# ul-12.net
KiCad netlist of a schematic drawn in EAGLE
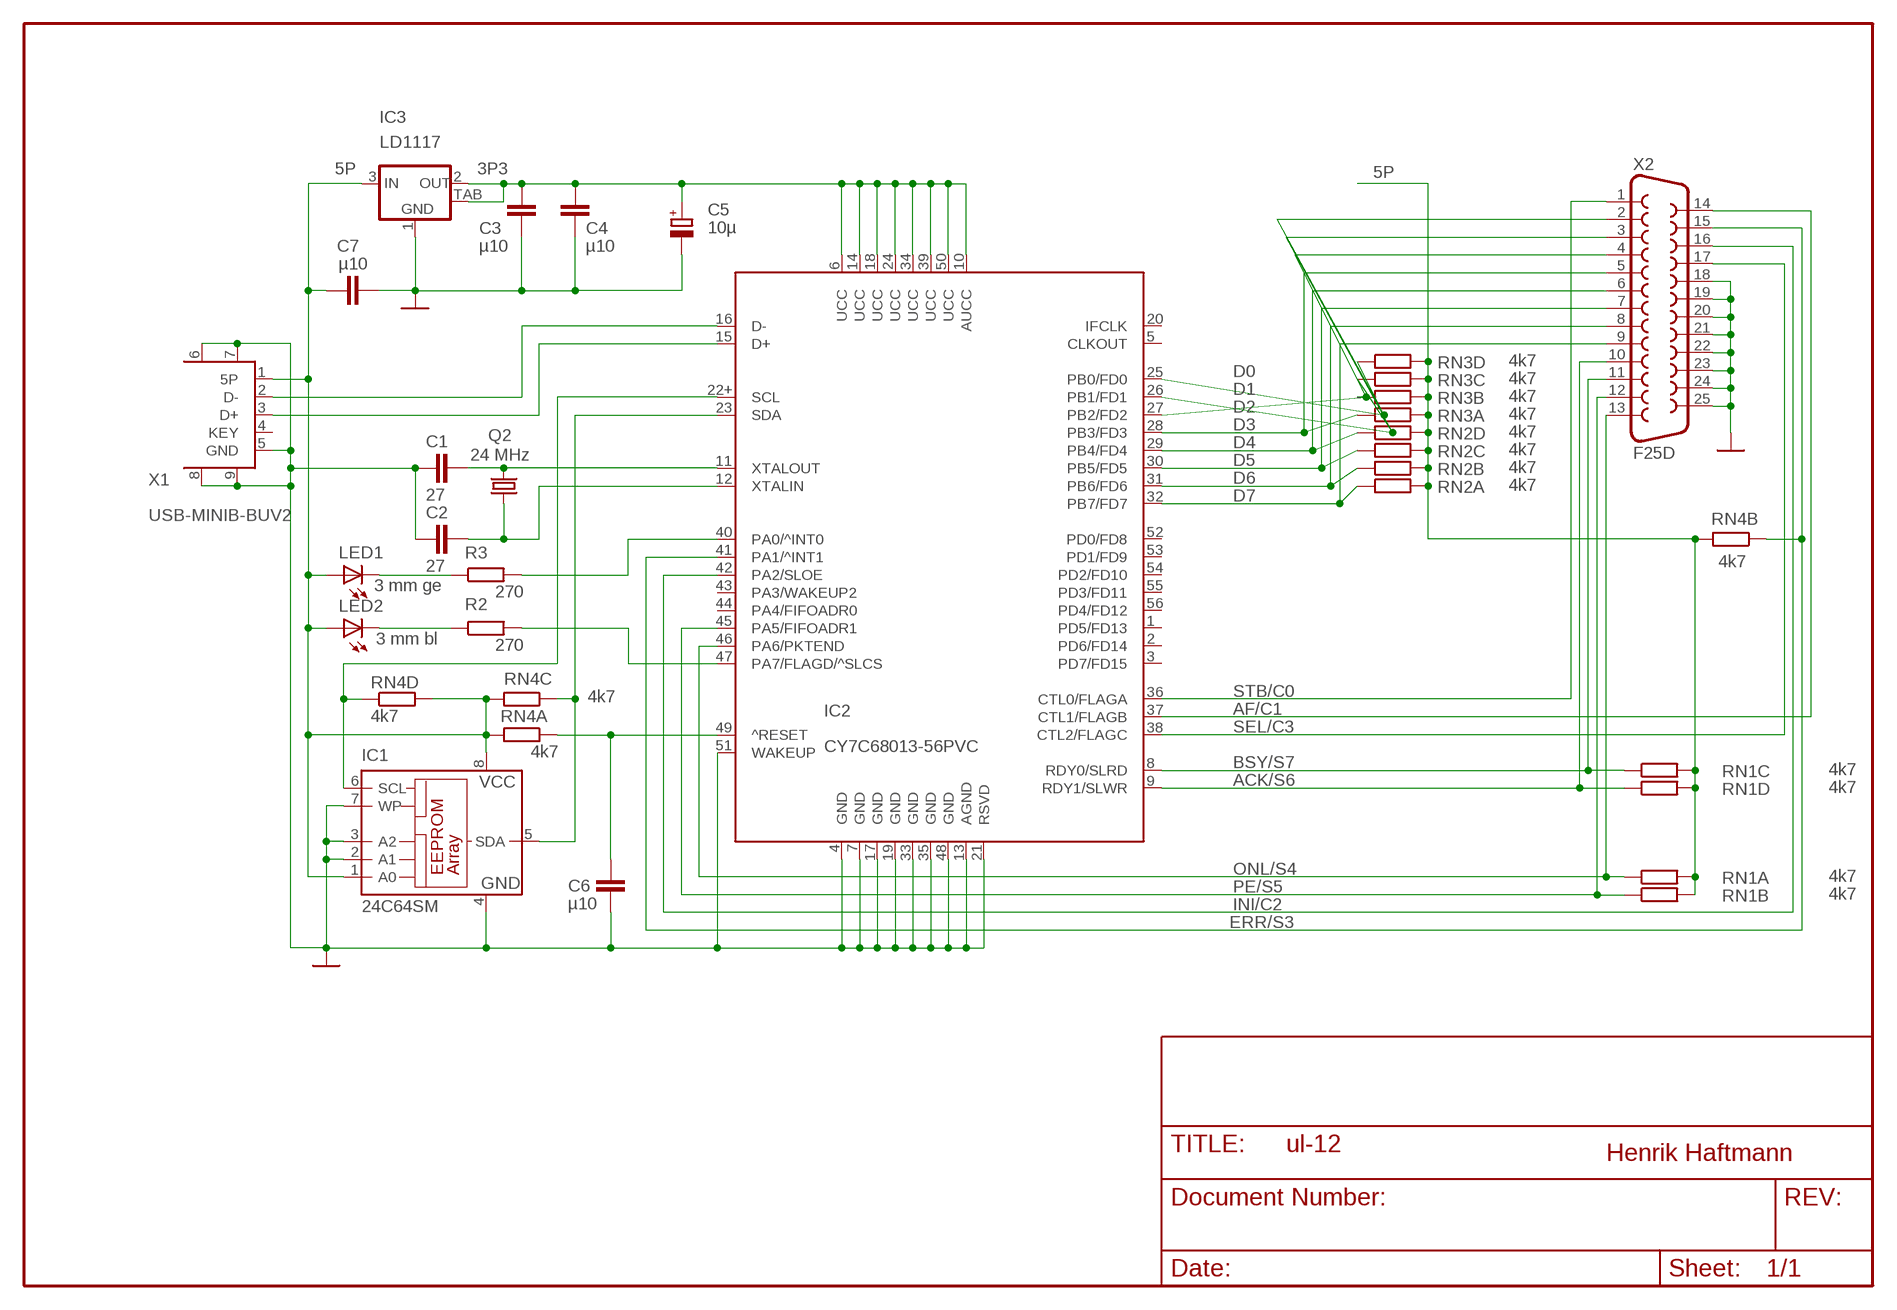
[diagram p0: schematic, sheet 1, part 1 of 2]
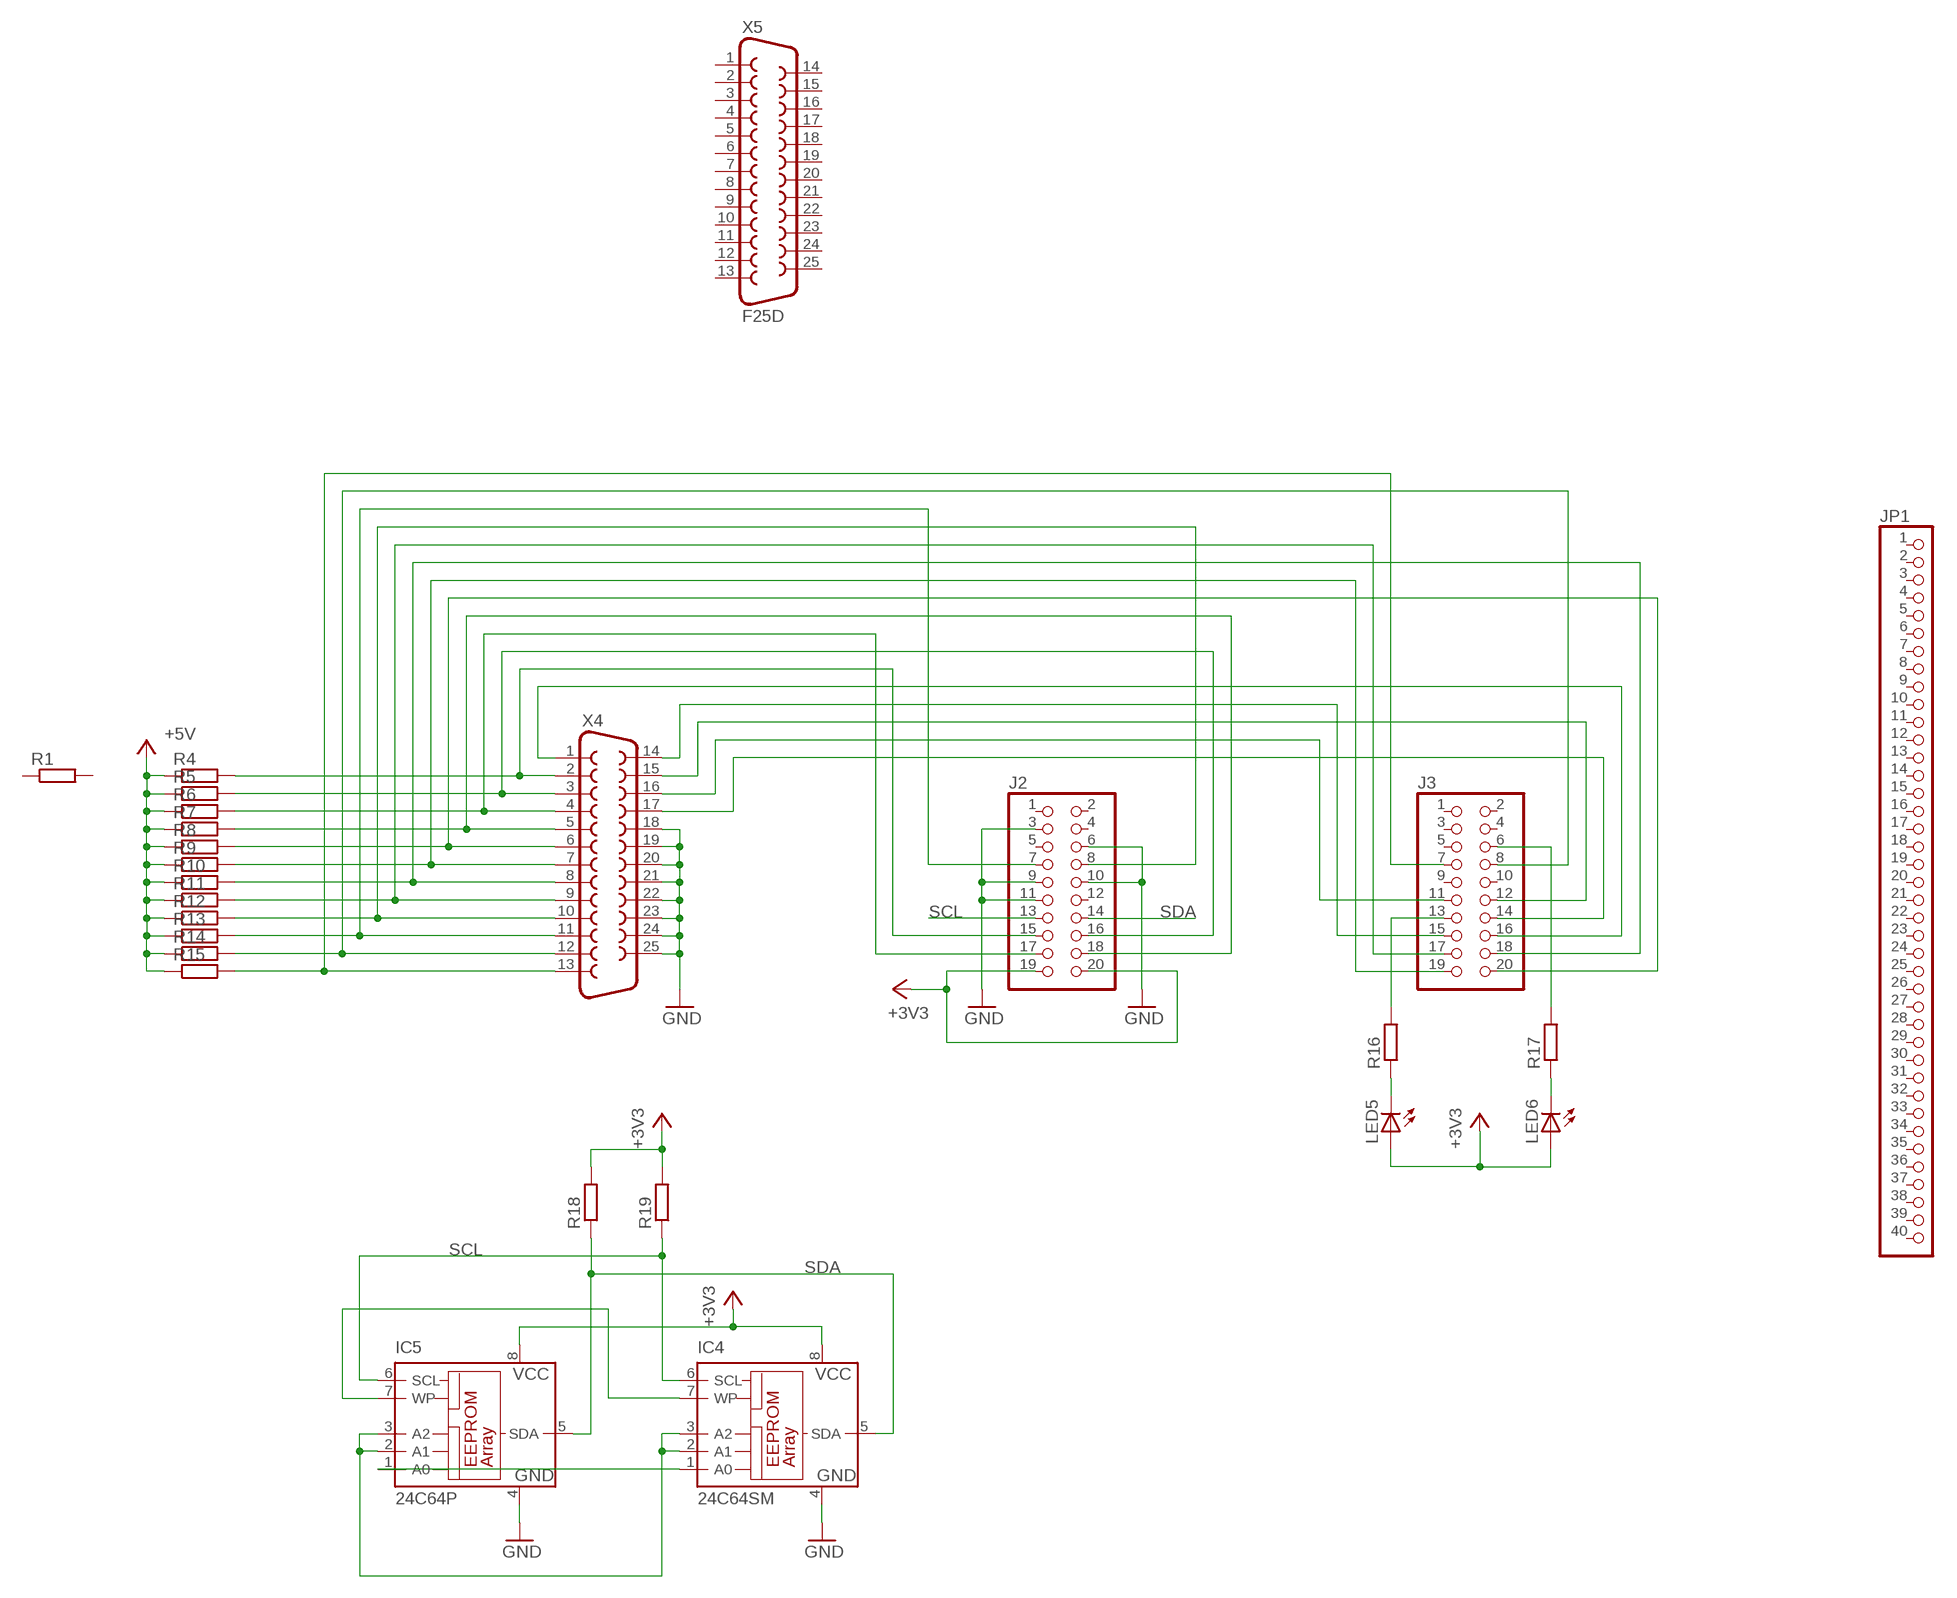
[diagram p1: schematic, sheet 1, part 2 of 2]

(export (version "E")
  (design (tool "Eeschema 10.0.6"))
  (components
    (comp (ref "C1")
      (value "27")
      (footprint "eagle-import:C0805")
      (libsource (lib "eagle-import") (part "C-EUC0805"))
    )
    (comp (ref "C2")
      (value "27")
      (footprint "eagle-import:C0805")
      (libsource (lib "eagle-import") (part "C-EUC0805"))
    )
    (comp (ref "C3")
      (value "µ10")
      (footprint "eagle-import:C0805")
      (libsource (lib "eagle-import") (part "C-EUC0805"))
    )
    (comp (ref "C4")
      (value "µ10")
      (footprint "eagle-import:C0805")
      (libsource (lib "eagle-import") (part "C-EUC0805"))
    )
    (comp (ref "C5")
      (value "10µ")
      (footprint "eagle-import:C_6032-28R")
      (libsource (lib "eagle-import") (part "CPOL-EUC/6032-28R"))
    )
    (comp (ref "C6")
      (value "µ10")
      (footprint "eagle-import:C0805")
      (libsource (lib "eagle-import") (part "C-EUC0805"))
    )
    (comp (ref "C7")
      (value "µ10")
      (footprint "eagle-import:C0805")
      (libsource (lib "eagle-import") (part "C-EUC0805"))
    )
    (comp (ref "IC1")
      (value "24C64SM")
      (footprint "eagle-import:SO-08M")
      (libsource (lib "eagle-import") (part "24SMC64"))
    )
    (comp (ref "IC2")
      (value "CY7C68013-56PVC")
      (footprint "eagle-import:SSOP56")
      (libsource (lib "eagle-import") (part "CY7C68013-56PVC"))
    )
    (comp (ref "IC3")
      (value "LD1117")
      (footprint "eagle-import:SOT223")
      (libsource (lib "eagle-import") (part "LD1117S"))
    )
    (comp (ref "IC4")
      (value "24C64SM")
      (footprint "eagle-import:SO-08M")
      (libsource (lib "eagle-import") (part "24SMC64"))
    )
    (comp (ref "IC5")
      (value "24C64P")
      (footprint "eagle-import:DIL8")
      (libsource (lib "eagle-import") (part "24PC64"))
    )
    (comp (ref "J2")
      (value "PINHD-2X10")
      (footprint "eagle-import:2X10")
      (libsource (lib "eagle-import") (part "PINHD-2X10"))
    )
    (comp (ref "J3")
      (value "PINHD-2X10")
      (footprint "eagle-import:2X10")
      (libsource (lib "eagle-import") (part "PINHD-2X10"))
    )
    (comp (ref "JP1")
      (value "PINHD-1X40")
      (footprint "eagle-import:1X40")
      (libsource (lib "eagle-import") (part "PINHD-1X40"))
    )
    (comp (ref "LED1")
      (value "3 mm ge")
      (footprint "eagle-import:LED3MM")
      (libsource (lib "eagle-import") (part "LED3MM"))
    )
    (comp (ref "LED2")
      (value "3 mm bl")
      (footprint "eagle-import:LED3MM")
      (libsource (lib "eagle-import") (part "LED3MM"))
    )
    (comp (ref "LED5")
      (value "LEDSML0805")
      (footprint "eagle-import:SML0805")
      (libsource (lib "eagle-import") (part "LEDSML0805"))
    )
    (comp (ref "LED6")
      (value "LEDSML0805")
      (footprint "eagle-import:SML0805")
      (libsource (lib "eagle-import") (part "LEDSML0805"))
    )
    (comp (ref "Q2")
      (value "24 MHz")
      (footprint "eagle-import:HC49U-V")
      (libsource (lib "eagle-import") (part "CRYTALHC49U-V"))
    )
    (comp (ref "R1")
      (value "R-EU_R0805")
      (footprint "eagle-import:R0805")
      (libsource (lib "eagle-import") (part "R-EU_R0805"))
    )
    (comp (ref "R2")
      (value "270")
      (footprint "eagle-import:R0805")
      (libsource (lib "eagle-import") (part "R-EU_R0805"))
    )
    (comp (ref "R3")
      (value "270")
      (footprint "eagle-import:R0805")
      (libsource (lib "eagle-import") (part "R-EU_R0805"))
    )
    (comp (ref "R4")
      (value "R-EU_R0805")
      (footprint "eagle-import:R0805")
      (libsource (lib "eagle-import") (part "R-EU_R0805"))
    )
    (comp (ref "R5")
      (value "R-EU_R0805")
      (footprint "eagle-import:R0805")
      (libsource (lib "eagle-import") (part "R-EU_R0805"))
    )
    (comp (ref "R6")
      (value "R-EU_R0805")
      (footprint "eagle-import:R0805")
      (libsource (lib "eagle-import") (part "R-EU_R0805"))
    )
    (comp (ref "R7")
      (value "R-EU_R0805")
      (footprint "eagle-import:R0805")
      (libsource (lib "eagle-import") (part "R-EU_R0805"))
    )
    (comp (ref "R8")
      (value "R-EU_R0805")
      (footprint "eagle-import:R0805")
      (libsource (lib "eagle-import") (part "R-EU_R0805"))
    )
    (comp (ref "R9")
      (value "R-EU_R0805")
      (footprint "eagle-import:R0805")
      (libsource (lib "eagle-import") (part "R-EU_R0805"))
    )
    (comp (ref "R10")
      (value "R-EU_R0805")
      (footprint "eagle-import:R0805")
      (libsource (lib "eagle-import") (part "R-EU_R0805"))
    )
    (comp (ref "R11")
      (value "R-EU_R0805")
      (footprint "eagle-import:R0805")
      (libsource (lib "eagle-import") (part "R-EU_R0805"))
    )
    (comp (ref "R12")
      (value "R-EU_R0805")
      (footprint "eagle-import:R0805")
      (libsource (lib "eagle-import") (part "R-EU_R0805"))
    )
    (comp (ref "R13")
      (value "R-EU_R0805")
      (footprint "eagle-import:R0805")
      (libsource (lib "eagle-import") (part "R-EU_R0805"))
    )
    (comp (ref "R14")
      (value "R-EU_R0805")
      (footprint "eagle-import:R0805")
      (libsource (lib "eagle-import") (part "R-EU_R0805"))
    )
    (comp (ref "R15")
      (value "R-EU_R0805")
      (footprint "eagle-import:R0805")
      (libsource (lib "eagle-import") (part "R-EU_R0805"))
    )
    (comp (ref "R16")
      (value "R-EU_0207/12")
      (footprint "eagle-import:0207_12")
      (libsource (lib "eagle-import") (part "R-EU_0207/12"))
    )
    (comp (ref "R17")
      (value "R-EU_0207/12")
      (footprint "eagle-import:0207_12")
      (libsource (lib "eagle-import") (part "R-EU_0207/12"))
    )
    (comp (ref "R18")
      (value "R-EU_R0805")
      (footprint "eagle-import:R0805")
      (libsource (lib "eagle-import") (part "R-EU_R0805"))
    )
    (comp (ref "R19")
      (value "R-EU_R0805")
      (footprint "eagle-import:R0805")
      (libsource (lib "eagle-import") (part "R-EU_R0805"))
    )
    (comp (ref "RN1")
      (value "4k7")
      (footprint "eagle-import:R-4P")
      (libsource (lib "eagle-import") (part "RN-4P1206"))
    )
    (comp (ref "RN2")
      (value "4k7")
      (footprint "eagle-import:R-4P")
      (libsource (lib "eagle-import") (part "RN-4P1206"))
    )
    (comp (ref "RN3")
      (value "4k7")
      (footprint "eagle-import:R-4P")
      (libsource (lib "eagle-import") (part "RN-4P1206"))
    )
    (comp (ref "RN4")
      (value "4k7")
      (footprint "eagle-import:R-4P")
      (libsource (lib "eagle-import") (part "RN-4P1206"))
    )
    (comp (ref "X1")
      (value "USB-MINIB-BUV2")
      (footprint "eagle-import:USB-MINIB-BUO")
      (libsource (lib "eagle-import") (part "USB-MINIB-BUV2"))
    )
    (comp (ref "X2")
      (value "F25D")
      (footprint "eagle-import:F25D")
      (libsource (lib "eagle-import") (part "hs-ul_F25D"))
    )
    (comp (ref "X4")
      (value "F25HP")
      (footprint "eagle-import:F25HP")
      (libsource (lib "eagle-import") (part "F25HP"))
    )
    (comp (ref "X5")
      (value "F25D")
      (footprint "eagle-import:F25D")
      (libsource (lib "eagle-import") (part "hs-ul_F25D"))
    )
  )
  (nets
    (net (code "1") (name "+3V3") (class "Default")
      (node (ref "IC4") (pin "8") (pinfunction "VCC_8") (pintype "power_in"))
      (node (ref "IC5") (pin "8") (pinfunction "VCC_8") (pintype "power_in"))
      (node (ref "J2") (pin "19") (pinfunction "19_19") (pintype "passive"))
      (node (ref "J2") (pin "20") (pinfunction "20_20") (pintype "passive"))
      (node (ref "LED5") (pin "A") (pinfunction "A_A") (pintype "passive"))
      (node (ref "LED6") (pin "A") (pinfunction "A_A") (pintype "passive"))
      (node (ref "R18") (pin "2") (pinfunction "2_2") (pintype "passive"))
      (node (ref "R19") (pin "2") (pinfunction "2_2") (pintype "passive"))
    )
    (net (code "2") (name "+5V") (class "Default")
      (node (ref "R10") (pin "1") (pinfunction "1_1") (pintype "passive"))
      (node (ref "R11") (pin "1") (pinfunction "1_1") (pintype "passive"))
      (node (ref "R12") (pin "1") (pinfunction "1_1") (pintype "passive"))
      (node (ref "R13") (pin "1") (pinfunction "1_1") (pintype "passive"))
      (node (ref "R14") (pin "1") (pinfunction "1_1") (pintype "passive"))
      (node (ref "R15") (pin "1") (pinfunction "1_1") (pintype "passive"))
      (node (ref "R4") (pin "1") (pinfunction "1_1") (pintype "passive"))
      (node (ref "R5") (pin "1") (pinfunction "1_1") (pintype "passive"))
      (node (ref "R6") (pin "1") (pinfunction "1_1") (pintype "passive"))
      (node (ref "R7") (pin "1") (pinfunction "1_1") (pintype "passive"))
      (node (ref "R8") (pin "1") (pinfunction "1_1") (pintype "passive"))
      (node (ref "R9") (pin "1") (pinfunction "1_1") (pintype "passive"))
    )
    (net (code "3") (name "/3P3") (class "Default")
      (node (ref "C3") (pin "2") (pinfunction "2_2") (pintype "passive"))
      (node (ref "C4") (pin "2") (pinfunction "2_2") (pintype "passive"))
      (node (ref "C5") (pin "+") (pinfunction "+_+") (pintype "passive"))
      (node (ref "IC2") (pin "10") (pinfunction "AUCC_10") (pintype "power_in"))
      (node (ref "IC2") (pin "14") (pinfunction "UCC_14") (pintype "power_in"))
      (node (ref "IC2") (pin "18") (pinfunction "UCC_18") (pintype "power_in"))
      (node (ref "IC2") (pin "24") (pinfunction "UCC_24") (pintype "power_in"))
      (node (ref "IC2") (pin "34") (pinfunction "UCC_34") (pintype "power_in"))
      (node (ref "IC2") (pin "39") (pinfunction "UCC_39") (pintype "power_in"))
      (node (ref "IC2") (pin "50") (pinfunction "UCC_50") (pintype "power_in"))
      (node (ref "IC2") (pin "6") (pinfunction "UCC_6") (pintype "power_in"))
      (node (ref "IC3") (pin "2") (pinfunction "OUT_2") (pintype "passive"))
      (node (ref "IC3") (pin "TAB") (pinfunction "OUT_TAB") (pintype "passive"))
    )
    (net (code "4") (name "/5P") (class "Default")
      (node (ref "C7") (pin "2") (pinfunction "2_2") (pintype "passive"))
      (node (ref "IC1") (pin "1") (pinfunction "A0_1") (pintype "input"))
      (node (ref "IC1") (pin "8") (pinfunction "VCC_8") (pintype "power_in"))
      (node (ref "IC3") (pin "3") (pinfunction "IN_3") (pintype "input"))
      (node (ref "LED1") (pin "A") (pinfunction "A_A") (pintype "passive"))
      (node (ref "LED2") (pin "A") (pinfunction "A_A") (pintype "passive"))
      (node (ref "RN1") (pin "5") (pinfunction "2_5") (pintype "passive"))
      (node (ref "RN1") (pin "6") (pinfunction "2_6") (pintype "passive"))
      (node (ref "RN1") (pin "7") (pinfunction "2_7") (pintype "passive"))
      (node (ref "RN1") (pin "8") (pinfunction "2_8") (pintype "passive"))
      (node (ref "RN2") (pin "5") (pinfunction "2_5") (pintype "passive"))
      (node (ref "RN2") (pin "6") (pinfunction "2_6") (pintype "passive"))
      (node (ref "RN2") (pin "7") (pinfunction "2_7") (pintype "passive"))
      (node (ref "RN2") (pin "8") (pinfunction "2_8") (pintype "passive"))
      (node (ref "RN3") (pin "5") (pinfunction "2_5") (pintype "passive"))
      (node (ref "RN3") (pin "6") (pinfunction "2_6") (pintype "passive"))
      (node (ref "RN3") (pin "7") (pinfunction "2_7") (pintype "passive"))
      (node (ref "RN3") (pin "8") (pinfunction "2_8") (pintype "passive"))
      (node (ref "RN4") (pin "5") (pinfunction "2_5") (pintype "passive"))
      (node (ref "RN4") (pin "6") (pinfunction "2_6") (pintype "passive"))
      (node (ref "RN4") (pin "7") (pinfunction "2_7") (pintype "passive"))
      (node (ref "RN4") (pin "8") (pinfunction "2_8") (pintype "passive"))
      (node (ref "X1") (pin "1") (pinfunction "5P_1") (pintype "power_in"))
    )
    (net (code "5") (name "/ACK{slash}S6") (class "Default")
      (node (ref "IC2") (pin "9") (pinfunction "RDY1/SLWR_9") (pintype "input"))
      (node (ref "RN1") (pin "4") (pinfunction "1_4") (pintype "passive"))
      (node (ref "X2") (pin "10") (pinfunction "10_10") (pintype "passive"))
    )
    (net (code "6") (name "/AF{slash}C1") (class "Default")
      (node (ref "IC2") (pin "37") (pinfunction "CTL1/FLAGB_37") (pintype "tri_state"))
      (node (ref "X2") (pin "14") (pinfunction "14_14") (pintype "passive"))
    )
    (net (code "7") (name "/BSY{slash}S7") (class "Default")
      (node (ref "IC2") (pin "8") (pinfunction "RDY0/SLRD_8") (pintype "input"))
      (node (ref "RN1") (pin "3") (pinfunction "1_3") (pintype "passive"))
      (node (ref "X2") (pin "11") (pinfunction "11_11") (pintype "passive"))
    )
    (net (code "8") (name "/D0") (class "Default")
      (node (ref "IC2") (pin "25") (pinfunction "PB0/FD0_25") (pintype "bidirectional"))
      (node (ref "RN3") (pin "4") (pinfunction "1_4") (pintype "passive"))
      (node (ref "X2") (pin "2") (pinfunction "2_2") (pintype "passive"))
    )
    (net (code "9") (name "/D1") (class "Default")
      (node (ref "IC2") (pin "26") (pinfunction "PB1/FD1_26") (pintype "bidirectional"))
      (node (ref "RN3") (pin "3") (pinfunction "1_3") (pintype "passive"))
      (node (ref "X2") (pin "3") (pinfunction "3_3") (pintype "passive"))
    )
    (net (code "10") (name "/D2") (class "Default")
      (node (ref "IC2") (pin "27") (pinfunction "PB2/FD2_27") (pintype "bidirectional"))
      (node (ref "RN3") (pin "2") (pinfunction "1_2") (pintype "passive"))
      (node (ref "X2") (pin "4") (pinfunction "4_4") (pintype "passive"))
    )
    (net (code "11") (name "/D3") (class "Default")
      (node (ref "IC2") (pin "28") (pinfunction "PB3/FD3_28") (pintype "bidirectional"))
      (node (ref "RN3") (pin "1") (pinfunction "1_1") (pintype "passive"))
      (node (ref "X2") (pin "5") (pinfunction "5_5") (pintype "passive"))
    )
    (net (code "12") (name "/D4") (class "Default")
      (node (ref "IC2") (pin "29") (pinfunction "PB4/FD4_29") (pintype "bidirectional"))
      (node (ref "RN2") (pin "4") (pinfunction "1_4") (pintype "passive"))
      (node (ref "X2") (pin "6") (pinfunction "6_6") (pintype "passive"))
    )
    (net (code "13") (name "/D5") (class "Default")
      (node (ref "IC2") (pin "30") (pinfunction "PB5/FD5_30") (pintype "bidirectional"))
      (node (ref "RN2") (pin "3") (pinfunction "1_3") (pintype "passive"))
      (node (ref "X2") (pin "7") (pinfunction "7_7") (pintype "passive"))
    )
    (net (code "14") (name "/D6") (class "Default")
      (node (ref "IC2") (pin "31") (pinfunction "PB6/FD6_31") (pintype "bidirectional"))
      (node (ref "RN2") (pin "2") (pinfunction "1_2") (pintype "passive"))
      (node (ref "X2") (pin "8") (pinfunction "8_8") (pintype "passive"))
    )
    (net (code "15") (name "/D7") (class "Default")
      (node (ref "IC2") (pin "32") (pinfunction "PB7/FD7_32") (pintype "bidirectional"))
      (node (ref "RN2") (pin "1") (pinfunction "1_1") (pintype "passive"))
      (node (ref "X2") (pin "9") (pinfunction "9_9") (pintype "passive"))
    )
    (net (code "16") (name "/ERR{slash}S3") (class "Default")
      (node (ref "IC2") (pin "41") (pinfunction "PA1/^INT1_41") (pintype "bidirectional"))
      (node (ref "RN4") (pin "2") (pinfunction "1_2") (pintype "passive"))
      (node (ref "X2") (pin "15") (pinfunction "15_15") (pintype "passive"))
    )
    (net (code "17") (name "/INI{slash}C2") (class "Default")
      (node (ref "IC2") (pin "42") (pinfunction "PA2/SLOE_42") (pintype "bidirectional"))
      (node (ref "X2") (pin "16") (pinfunction "16_16") (pintype "passive"))
    )
    (net (code "18") (name "/ONL{slash}S4") (class "Default")
      (node (ref "IC2") (pin "46") (pinfunction "PA6/PKTEND_46") (pintype "bidirectional"))
      (node (ref "RN1") (pin "1") (pinfunction "1_1") (pintype "passive"))
      (node (ref "X2") (pin "13") (pinfunction "13_13") (pintype "passive"))
    )
    (net (code "19") (name "/PE{slash}S5") (class "Default")
      (node (ref "IC2") (pin "45") (pinfunction "PA5/FIFOADR1_45") (pintype "bidirectional"))
      (node (ref "RN1") (pin "2") (pinfunction "1_2") (pintype "passive"))
      (node (ref "X2") (pin "12") (pinfunction "12_12") (pintype "passive"))
    )
    (net (code "20") (name "/SCL") (class "Default")
      (node (ref "IC4") (pin "6") (pinfunction "SCL_6") (pintype "input"))
      (node (ref "IC5") (pin "6") (pinfunction "SCL_6") (pintype "input"))
      (node (ref "J2") (pin "13") (pinfunction "13_13") (pintype "passive"))
      (node (ref "R19") (pin "1") (pinfunction "1_1") (pintype "passive"))
    )
    (net (code "21") (name "/SDA") (class "Default")
      (node (ref "IC4") (pin "5") (pinfunction "SDA_5") (pintype "bidirectional"))
      (node (ref "IC5") (pin "5") (pinfunction "SDA_5") (pintype "bidirectional"))
      (node (ref "J2") (pin "14") (pinfunction "14_14") (pintype "passive"))
      (node (ref "R18") (pin "1") (pinfunction "1_1") (pintype "passive"))
    )
    (net (code "22") (name "/SEL{slash}C3") (class "Default")
      (node (ref "IC2") (pin "38") (pinfunction "CTL2/FLAGC_38") (pintype "tri_state"))
      (node (ref "X2") (pin "17") (pinfunction "17_17") (pintype "passive"))
    )
    (net (code "23") (name "/STB{slash}C0") (class "Default")
      (node (ref "IC2") (pin "36") (pinfunction "CTL0/FLAGA_36") (pintype "tri_state"))
      (node (ref "X2") (pin "1") (pinfunction "1_1") (pintype "passive"))
    )
    (net (code "24") (name "GND") (class "Default")
      (node (ref "C1") (pin "2") (pinfunction "2_2") (pintype "passive"))
      (node (ref "C2") (pin "2") (pinfunction "2_2") (pintype "passive"))
      (node (ref "C3") (pin "1") (pinfunction "1_1") (pintype "passive"))
      (node (ref "C4") (pin "1") (pinfunction "1_1") (pintype "passive"))
      (node (ref "C5") (pin "-") (pinfunction "-_-") (pintype "passive"))
      (node (ref "C6") (pin "1") (pinfunction "1_1") (pintype "passive"))
      (node (ref "C7") (pin "1") (pinfunction "1_1") (pintype "passive"))
      (node (ref "IC1") (pin "2") (pinfunction "A1_2") (pintype "input"))
      (node (ref "IC1") (pin "3") (pinfunction "A2_3") (pintype "input"))
      (node (ref "IC1") (pin "4") (pinfunction "GND_4") (pintype "power_in"))
      (node (ref "IC1") (pin "7") (pinfunction "WP_7") (pintype "input"))
      (node (ref "IC2") (pin "13") (pinfunction "AGND_13") (pintype "power_in"))
      (node (ref "IC2") (pin "17") (pinfunction "GND_17") (pintype "power_in"))
      (node (ref "IC2") (pin "19") (pinfunction "GND_19") (pintype "power_in"))
      (node (ref "IC2") (pin "21") (pinfunction "RSVD_21") (pintype "input"))
      (node (ref "IC2") (pin "33") (pinfunction "GND_33") (pintype "power_in"))
      (node (ref "IC2") (pin "35") (pinfunction "GND_35") (pintype "power_in"))
      (node (ref "IC2") (pin "4") (pinfunction "GND_4") (pintype "power_in"))
      (node (ref "IC2") (pin "48") (pinfunction "GND_48") (pintype "power_in"))
      (node (ref "IC2") (pin "51") (pinfunction "WAKEUP_51") (pintype "input"))
      (node (ref "IC2") (pin "7") (pinfunction "GND_7") (pintype "power_in"))
      (node (ref "IC3") (pin "1") (pinfunction "GND_1") (pintype "power_in"))
      (node (ref "IC4") (pin "4") (pinfunction "GND_4") (pintype "power_in"))
      (node (ref "IC5") (pin "4") (pinfunction "GND_4") (pintype "power_in"))
      (node (ref "J2") (pin "10") (pinfunction "10_10") (pintype "passive"))
      (node (ref "J2") (pin "11") (pinfunction "11_11") (pintype "passive"))
      (node (ref "J2") (pin "3") (pinfunction "3_3") (pintype "passive"))
      (node (ref "J2") (pin "6") (pinfunction "6_6") (pintype "passive"))
      (node (ref "J2") (pin "9") (pinfunction "9_9") (pintype "passive"))
      (node (ref "X1") (pin "5") (pinfunction "GND_5") (pintype "power_in"))
      (node (ref "X1") (pin "6") (pinfunction "GND_6") (pintype "power_in"))
      (node (ref "X1") (pin "7") (pinfunction "GND_7") (pintype "power_in"))
      (node (ref "X1") (pin "8") (pinfunction "GND_8") (pintype "power_in"))
      (node (ref "X1") (pin "9") (pinfunction "GND_9") (pintype "power_in"))
      (node (ref "X2") (pin "18") (pinfunction "18_18") (pintype "passive"))
      (node (ref "X2") (pin "19") (pinfunction "19_19") (pintype "passive"))
      (node (ref "X2") (pin "20") (pinfunction "20_20") (pintype "passive"))
      (node (ref "X2") (pin "21") (pinfunction "21_21") (pintype "passive"))
      (node (ref "X2") (pin "22") (pinfunction "22_22") (pintype "passive"))
      (node (ref "X2") (pin "23") (pinfunction "23_23") (pintype "passive"))
      (node (ref "X2") (pin "24") (pinfunction "24_24") (pintype "passive"))
      (node (ref "X2") (pin "25") (pinfunction "25_25") (pintype "passive"))
      (node (ref "X4") (pin "18") (pinfunction "18_18") (pintype "passive"))
      (node (ref "X4") (pin "19") (pinfunction "19_19") (pintype "passive"))
      (node (ref "X4") (pin "20") (pinfunction "20_20") (pintype "passive"))
      (node (ref "X4") (pin "21") (pinfunction "21_21") (pintype "passive"))
      (node (ref "X4") (pin "22") (pinfunction "22_22") (pintype "passive"))
      (node (ref "X4") (pin "23") (pinfunction "23_23") (pintype "passive"))
      (node (ref "X4") (pin "24") (pinfunction "24_24") (pintype "passive"))
      (node (ref "X4") (pin "25") (pinfunction "25_25") (pintype "passive"))
    )
    (net (code "25") (name "Net-(IC1-SCL)") (class "Default")
      (node (ref "IC1") (pin "6") (pinfunction "SCL_6") (pintype "input"))
      (node (ref "IC2") (pin "22+") (pinfunction "SCL_22+") (pintype "open_collector"))
      (node (ref "RN4") (pin "4") (pinfunction "1_4") (pintype "passive"))
    )
    (net (code "26") (name "Net-(IC1-SDA)") (class "Default")
      (node (ref "IC1") (pin "5") (pinfunction "SDA_5") (pintype "bidirectional"))
      (node (ref "IC2") (pin "23") (pinfunction "SDA_23") (pintype "open_collector"))
      (node (ref "RN4") (pin "3") (pinfunction "1_3") (pintype "passive"))
    )
    (net (code "27") (name "Net-(IC2-D+)") (class "Default")
      (node (ref "IC2") (pin "15") (pinfunction "D+_15") (pintype "bidirectional"))
      (node (ref "X1") (pin "3") (pinfunction "D+_3") (pintype "bidirectional"))
    )
    (net (code "28") (name "Net-(IC2-D-)") (class "Default")
      (node (ref "IC2") (pin "16") (pinfunction "D-_16") (pintype "bidirectional"))
      (node (ref "X1") (pin "2") (pinfunction "D-_2") (pintype "bidirectional"))
    )
    (net (code "29") (name "Net-(IC2-PA0{slash}^INT0)") (class "Default")
      (node (ref "IC2") (pin "40") (pinfunction "PA0/^INT0_40") (pintype "bidirectional"))
      (node (ref "R3") (pin "2") (pinfunction "2_2") (pintype "passive"))
    )
    (net (code "30") (name "Net-(IC2-PA7{slash}FLAGD{slash}^SLCS)") (class "Default")
      (node (ref "IC2") (pin "47") (pinfunction "PA7/FLAGD/^SLCS_47") (pintype "bidirectional"))
      (node (ref "R2") (pin "2") (pinfunction "2_2") (pintype "passive"))
    )
    (net (code "31") (name "Net-(IC2-XTALIN)") (class "Default")
      (node (ref "C2") (pin "1") (pinfunction "1_1") (pintype "passive"))
      (node (ref "IC2") (pin "12") (pinfunction "XTALIN_12") (pintype "input"))
      (node (ref "Q2") (pin "1") (pinfunction "1_1") (pintype "passive"))
    )
    (net (code "32") (name "Net-(IC2-XTALOUT)") (class "Default")
      (node (ref "C1") (pin "1") (pinfunction "1_1") (pintype "passive"))
      (node (ref "IC2") (pin "11") (pinfunction "XTALOUT_11") (pintype "output"))
      (node (ref "Q2") (pin "2") (pinfunction "2_2") (pintype "passive"))
    )
    (net (code "33") (name "Net-(IC2-^RESET)") (class "Default")
      (node (ref "C6") (pin "2") (pinfunction "2_2") (pintype "passive"))
      (node (ref "IC2") (pin "49") (pinfunction "^RESET_49") (pintype "input"))
      (node (ref "RN4") (pin "1") (pinfunction "1_1") (pintype "passive"))
    )
    (net (code "34") (name "Net-(IC4-A0)") (class "Default")
      (node (ref "IC4") (pin "1") (pinfunction "A0_1") (pintype "input"))
      (node (ref "IC5") (pin "1") (pinfunction "A0_1") (pintype "input"))
    )
    (net (code "35") (name "Net-(IC4-A1)") (class "Default")
      (node (ref "IC4") (pin "2") (pinfunction "A1_2") (pintype "input"))
      (node (ref "IC4") (pin "3") (pinfunction "A2_3") (pintype "input"))
      (node (ref "IC5") (pin "2") (pinfunction "A1_2") (pintype "input"))
      (node (ref "IC5") (pin "3") (pinfunction "A2_3") (pintype "input"))
    )
    (net (code "36") (name "Net-(IC4-WP)") (class "Default")
      (node (ref "IC4") (pin "7") (pinfunction "WP_7") (pintype "input"))
      (node (ref "IC5") (pin "7") (pinfunction "WP_7") (pintype "input"))
    )
    (net (code "37") (name "Net-(J2-Pad7)") (class "Default")
      (node (ref "J2") (pin "7") (pinfunction "7_7") (pintype "passive"))
      (node (ref "R13") (pin "2") (pinfunction "2_2") (pintype "passive"))
      (node (ref "X4") (pin "11") (pinfunction "11_11") (pintype "passive"))
    )
    (net (code "38") (name "Net-(J2-Pad8)") (class "Default")
      (node (ref "J2") (pin "8") (pinfunction "8_8") (pintype "passive"))
      (node (ref "R12") (pin "2") (pinfunction "2_2") (pintype "passive"))
      (node (ref "X4") (pin "10") (pinfunction "10_10") (pintype "passive"))
    )
    (net (code "39") (name "Net-(J2-Pad15)") (class "Default")
      (node (ref "J2") (pin "15") (pinfunction "15_15") (pintype "passive"))
      (node (ref "R4") (pin "2") (pinfunction "2_2") (pintype "passive"))
      (node (ref "X4") (pin "2") (pinfunction "2_2") (pintype "passive"))
    )
    (net (code "40") (name "Net-(J2-Pad16)") (class "Default")
      (node (ref "J2") (pin "16") (pinfunction "16_16") (pintype "passive"))
      (node (ref "R5") (pin "2") (pinfunction "2_2") (pintype "passive"))
      (node (ref "X4") (pin "3") (pinfunction "3_3") (pintype "passive"))
    )
    (net (code "41") (name "Net-(J2-Pad17)") (class "Default")
      (node (ref "J2") (pin "17") (pinfunction "17_17") (pintype "passive"))
      (node (ref "R6") (pin "2") (pinfunction "2_2") (pintype "passive"))
      (node (ref "X4") (pin "4") (pinfunction "4_4") (pintype "passive"))
    )
    (net (code "42") (name "Net-(J2-Pad18)") (class "Default")
      (node (ref "J2") (pin "18") (pinfunction "18_18") (pintype "passive"))
      (node (ref "R7") (pin "2") (pinfunction "2_2") (pintype "passive"))
      (node (ref "X4") (pin "5") (pinfunction "5_5") (pintype "passive"))
    )
    (net (code "43") (name "Net-(J3-Pad6)") (class "Default")
      (node (ref "J3") (pin "6") (pinfunction "6_6") (pintype "passive"))
      (node (ref "R17") (pin "2") (pinfunction "2_2") (pintype "passive"))
    )
    (net (code "44") (name "Net-(J3-Pad7)") (class "Default")
      (node (ref "J3") (pin "7") (pinfunction "7_7") (pintype "passive"))
      (node (ref "R15") (pin "2") (pinfunction "2_2") (pintype "passive"))
      (node (ref "X4") (pin "13") (pinfunction "13_13") (pintype "passive"))
    )
    (net (code "45") (name "Net-(J3-Pad8)") (class "Default")
      (node (ref "J3") (pin "8") (pinfunction "8_8") (pintype "passive"))
      (node (ref "R14") (pin "2") (pinfunction "2_2") (pintype "passive"))
      (node (ref "X4") (pin "12") (pinfunction "12_12") (pintype "passive"))
    )
    (net (code "46") (name "Net-(J3-Pad11)") (class "Default")
      (node (ref "J3") (pin "11") (pinfunction "11_11") (pintype "passive"))
      (node (ref "X4") (pin "16") (pinfunction "16_16") (pintype "passive"))
    )
    (net (code "47") (name "Net-(J3-Pad12)") (class "Default")
      (node (ref "J3") (pin "12") (pinfunction "12_12") (pintype "passive"))
      (node (ref "X4") (pin "15") (pinfunction "15_15") (pintype "passive"))
    )
    (net (code "48") (name "Net-(J3-Pad13)") (class "Default")
      (node (ref "J3") (pin "13") (pinfunction "13_13") (pintype "passive"))
      (node (ref "R16") (pin "2") (pinfunction "2_2") (pintype "passive"))
    )
    (net (code "49") (name "Net-(J3-Pad14)") (class "Default")
      (node (ref "J3") (pin "14") (pinfunction "14_14") (pintype "passive"))
      (node (ref "X4") (pin "17") (pinfunction "17_17") (pintype "passive"))
    )
    (net (code "50") (name "Net-(J3-Pad15)") (class "Default")
      (node (ref "J3") (pin "15") (pinfunction "15_15") (pintype "passive"))
      (node (ref "X4") (pin "14") (pinfunction "14_14") (pintype "passive"))
    )
    (net (code "51") (name "Net-(J3-Pad16)") (class "Default")
      (node (ref "J3") (pin "16") (pinfunction "16_16") (pintype "passive"))
      (node (ref "X4") (pin "1") (pinfunction "1_1") (pintype "passive"))
    )
    (net (code "52") (name "Net-(J3-Pad17)") (class "Default")
      (node (ref "J3") (pin "17") (pinfunction "17_17") (pintype "passive"))
      (node (ref "R11") (pin "2") (pinfunction "2_2") (pintype "passive"))
      (node (ref "X4") (pin "9") (pinfunction "9_9") (pintype "passive"))
    )
    (net (code "53") (name "Net-(J3-Pad18)") (class "Default")
      (node (ref "J3") (pin "18") (pinfunction "18_18") (pintype "passive"))
      (node (ref "R10") (pin "2") (pinfunction "2_2") (pintype "passive"))
      (node (ref "X4") (pin "8") (pinfunction "8_8") (pintype "passive"))
    )
    (net (code "54") (name "Net-(J3-Pad19)") (class "Default")
      (node (ref "J3") (pin "19") (pinfunction "19_19") (pintype "passive"))
      (node (ref "R9") (pin "2") (pinfunction "2_2") (pintype "passive"))
      (node (ref "X4") (pin "7") (pinfunction "7_7") (pintype "passive"))
    )
    (net (code "55") (name "Net-(J3-Pad20)") (class "Default")
      (node (ref "J3") (pin "20") (pinfunction "20_20") (pintype "passive"))
      (node (ref "R8") (pin "2") (pinfunction "2_2") (pintype "passive"))
      (node (ref "X4") (pin "6") (pinfunction "6_6") (pintype "passive"))
    )
    (net (code "56") (name "Net-(LED1-C)") (class "Default")
      (node (ref "LED1") (pin "K") (pinfunction "C_K") (pintype "passive"))
      (node (ref "R3") (pin "1") (pinfunction "1_1") (pintype "passive"))
    )
    (net (code "57") (name "Net-(LED2-C)") (class "Default")
      (node (ref "LED2") (pin "K") (pinfunction "C_K") (pintype "passive"))
      (node (ref "R2") (pin "1") (pinfunction "1_1") (pintype "passive"))
    )
    (net (code "58") (name "Net-(LED5-PadC)") (class "Default")
      (node (ref "LED5") (pin "C") (pinfunction "C_C") (pintype "passive"))
      (node (ref "R16") (pin "1") (pinfunction "1_1") (pintype "passive"))
    )
    (net (code "59") (name "Net-(LED6-PadC)") (class "Default")
      (node (ref "LED6") (pin "C") (pinfunction "C_C") (pintype "passive"))
      (node (ref "R17") (pin "1") (pinfunction "1_1") (pintype "passive"))
    )
    (net (code "60") (name "unconnected-(IC2-CLKOUT-Pad5)") (class "Default")
      (node (ref "IC2") (pin "5") (pinfunction "CLKOUT_5") (pintype "tri_state"))
    )
    (net (code "61") (name "unconnected-(IC2-IFCLK-Pad20)") (class "Default")
      (node (ref "IC2") (pin "20") (pinfunction "IFCLK_20") (pintype "bidirectional"))
    )
    (net (code "62") (name "unconnected-(IC2-PA3{slash}WAKEUP2-Pad43)") (class "Default")
      (node (ref "IC2") (pin "43") (pinfunction "PA3/WAKEUP2_43") (pintype "bidirectional"))
    )
    (net (code "63") (name "unconnected-(IC2-PA4{slash}FIFOADR0-Pad44)") (class "Default")
      (node (ref "IC2") (pin "44") (pinfunction "PA4/FIFOADR0_44") (pintype "bidirectional"))
    )
    (net (code "64") (name "unconnected-(IC2-PD0{slash}FD8-Pad52)") (class "Default")
      (node (ref "IC2") (pin "52") (pinfunction "PD0/FD8_52") (pintype "bidirectional"))
    )
    (net (code "65") (name "unconnected-(IC2-PD1{slash}FD9-Pad53)") (class "Default")
      (node (ref "IC2") (pin "53") (pinfunction "PD1/FD9_53") (pintype "bidirectional"))
    )
    (net (code "66") (name "unconnected-(IC2-PD2{slash}FD10-Pad54)") (class "Default")
      (node (ref "IC2") (pin "54") (pinfunction "PD2/FD10_54") (pintype "bidirectional"))
    )
    (net (code "67") (name "unconnected-(IC2-PD3{slash}FD11-Pad55)") (class "Default")
      (node (ref "IC2") (pin "55") (pinfunction "PD3/FD11_55") (pintype "bidirectional"))
    )
    (net (code "68") (name "unconnected-(IC2-PD4{slash}FD12-Pad56)") (class "Default")
      (node (ref "IC2") (pin "56") (pinfunction "PD4/FD12_56") (pintype "bidirectional"))
    )
    (net (code "69") (name "unconnected-(IC2-PD5{slash}FD13-Pad1)") (class "Default")
      (node (ref "IC2") (pin "1") (pinfunction "PD5/FD13_1") (pintype "bidirectional"))
    )
    (net (code "70") (name "unconnected-(IC2-PD6{slash}FD14-Pad2)") (class "Default")
      (node (ref "IC2") (pin "2") (pinfunction "PD6/FD14_2") (pintype "bidirectional"))
    )
    (net (code "71") (name "unconnected-(IC2-PD7{slash}FD15-Pad3)") (class "Default")
      (node (ref "IC2") (pin "3") (pinfunction "PD7/FD15_3") (pintype "bidirectional"))
    )
    (net (code "72") (name "unconnected-(J2-Pad1)") (class "Default")
      (node (ref "J2") (pin "1") (pinfunction "1_1") (pintype "passive"))
    )
    (net (code "73") (name "unconnected-(J2-Pad2)") (class "Default")
      (node (ref "J2") (pin "2") (pinfunction "2_2") (pintype "passive"))
    )
    (net (code "74") (name "unconnected-(J2-Pad4)") (class "Default")
      (node (ref "J2") (pin "4") (pinfunction "4_4") (pintype "passive"))
    )
    (net (code "75") (name "unconnected-(J2-Pad5)") (class "Default")
      (node (ref "J2") (pin "5") (pinfunction "5_5") (pintype "passive"))
    )
    (net (code "76") (name "unconnected-(J2-Pad12)") (class "Default")
      (node (ref "J2") (pin "12") (pinfunction "12_12") (pintype "passive"))
    )
    (net (code "77") (name "unconnected-(J3-Pad1)") (class "Default")
      (node (ref "J3") (pin "1") (pinfunction "1_1") (pintype "passive"))
    )
    (net (code "78") (name "unconnected-(J3-Pad2)") (class "Default")
      (node (ref "J3") (pin "2") (pinfunction "2_2") (pintype "passive"))
    )
    (net (code "79") (name "unconnected-(J3-Pad3)") (class "Default")
      (node (ref "J3") (pin "3") (pinfunction "3_3") (pintype "passive"))
    )
    (net (code "80") (name "unconnected-(J3-Pad4)") (class "Default")
      (node (ref "J3") (pin "4") (pinfunction "4_4") (pintype "passive"))
    )
    (net (code "81") (name "unconnected-(J3-Pad5)") (class "Default")
      (node (ref "J3") (pin "5") (pinfunction "5_5") (pintype "passive"))
    )
    (net (code "82") (name "unconnected-(J3-Pad9)") (class "Default")
      (node (ref "J3") (pin "9") (pinfunction "9_9") (pintype "passive"))
    )
    (net (code "83") (name "unconnected-(J3-Pad10)") (class "Default")
      (node (ref "J3") (pin "10") (pinfunction "10_10") (pintype "passive"))
    )
    (net (code "84") (name "unconnected-(JP1-Pad1)") (class "Default")
      (node (ref "JP1") (pin "1") (pinfunction "1_1") (pintype "passive"))
    )
    (net (code "85") (name "unconnected-(JP1-Pad2)") (class "Default")
      (node (ref "JP1") (pin "2") (pinfunction "2_2") (pintype "passive"))
    )
    (net (code "86") (name "unconnected-(JP1-Pad3)") (class "Default")
      (node (ref "JP1") (pin "3") (pinfunction "3_3") (pintype "passive"))
    )
    (net (code "87") (name "unconnected-(JP1-Pad4)") (class "Default")
      (node (ref "JP1") (pin "4") (pinfunction "4_4") (pintype "passive"))
    )
    (net (code "88") (name "unconnected-(JP1-Pad5)") (class "Default")
      (node (ref "JP1") (pin "5") (pinfunction "5_5") (pintype "passive"))
    )
    (net (code "89") (name "unconnected-(JP1-Pad6)") (class "Default")
      (node (ref "JP1") (pin "6") (pinfunction "6_6") (pintype "passive"))
    )
    (net (code "90") (name "unconnected-(JP1-Pad7)") (class "Default")
      (node (ref "JP1") (pin "7") (pinfunction "7_7") (pintype "passive"))
    )
    (net (code "91") (name "unconnected-(JP1-Pad8)") (class "Default")
      (node (ref "JP1") (pin "8") (pinfunction "8_8") (pintype "passive"))
    )
    (net (code "92") (name "unconnected-(JP1-Pad9)") (class "Default")
      (node (ref "JP1") (pin "9") (pinfunction "9_9") (pintype "passive"))
    )
    (net (code "93") (name "unconnected-(JP1-Pad10)") (class "Default")
      (node (ref "JP1") (pin "10") (pinfunction "10_10") (pintype "passive"))
    )
    (net (code "94") (name "unconnected-(JP1-Pad11)") (class "Default")
      (node (ref "JP1") (pin "11") (pinfunction "11_11") (pintype "passive"))
    )
    (net (code "95") (name "unconnected-(JP1-Pad12)") (class "Default")
      (node (ref "JP1") (pin "12") (pinfunction "12_12") (pintype "passive"))
    )
    (net (code "96") (name "unconnected-(JP1-Pad13)") (class "Default")
      (node (ref "JP1") (pin "13") (pinfunction "13_13") (pintype "passive"))
    )
    (net (code "97") (name "unconnected-(JP1-Pad14)") (class "Default")
      (node (ref "JP1") (pin "14") (pinfunction "14_14") (pintype "passive"))
    )
    (net (code "98") (name "unconnected-(JP1-Pad15)") (class "Default")
      (node (ref "JP1") (pin "15") (pinfunction "15_15") (pintype "passive"))
    )
    (net (code "99") (name "unconnected-(JP1-Pad16)") (class "Default")
      (node (ref "JP1") (pin "16") (pinfunction "16_16") (pintype "passive"))
    )
    (net (code "100") (name "unconnected-(JP1-Pad17)") (class "Default")
      (node (ref "JP1") (pin "17") (pinfunction "17_17") (pintype "passive"))
    )
    (net (code "101") (name "unconnected-(JP1-Pad18)") (class "Default")
      (node (ref "JP1") (pin "18") (pinfunction "18_18") (pintype "passive"))
    )
    (net (code "102") (name "unconnected-(JP1-Pad19)") (class "Default")
      (node (ref "JP1") (pin "19") (pinfunction "19_19") (pintype "passive"))
    )
    (net (code "103") (name "unconnected-(JP1-Pad20)") (class "Default")
      (node (ref "JP1") (pin "20") (pinfunction "20_20") (pintype "passive"))
    )
    (net (code "104") (name "unconnected-(JP1-Pad21)") (class "Default")
      (node (ref "JP1") (pin "21") (pinfunction "21_21") (pintype "passive"))
    )
    (net (code "105") (name "unconnected-(JP1-Pad22)") (class "Default")
      (node (ref "JP1") (pin "22") (pinfunction "22_22") (pintype "passive"))
    )
    (net (code "106") (name "unconnected-(JP1-Pad23)") (class "Default")
      (node (ref "JP1") (pin "23") (pinfunction "23_23") (pintype "passive"))
    )
    (net (code "107") (name "unconnected-(JP1-Pad24)") (class "Default")
      (node (ref "JP1") (pin "24") (pinfunction "24_24") (pintype "passive"))
    )
    (net (code "108") (name "unconnected-(JP1-Pad25)") (class "Default")
      (node (ref "JP1") (pin "25") (pinfunction "25_25") (pintype "passive"))
    )
    (net (code "109") (name "unconnected-(JP1-Pad26)") (class "Default")
      (node (ref "JP1") (pin "26") (pinfunction "26_26") (pintype "passive"))
    )
    (net (code "110") (name "unconnected-(JP1-Pad27)") (class "Default")
      (node (ref "JP1") (pin "27") (pinfunction "27_27") (pintype "passive"))
    )
    (net (code "111") (name "unconnected-(JP1-Pad28)") (class "Default")
      (node (ref "JP1") (pin "28") (pinfunction "28_28") (pintype "passive"))
    )
    (net (code "112") (name "unconnected-(JP1-Pad29)") (class "Default")
      (node (ref "JP1") (pin "29") (pinfunction "29_29") (pintype "passive"))
    )
    (net (code "113") (name "unconnected-(JP1-Pad30)") (class "Default")
      (node (ref "JP1") (pin "30") (pinfunction "30_30") (pintype "passive"))
    )
    (net (code "114") (name "unconnected-(JP1-Pad31)") (class "Default")
      (node (ref "JP1") (pin "31") (pinfunction "31_31") (pintype "passive"))
    )
    (net (code "115") (name "unconnected-(JP1-Pad32)") (class "Default")
      (node (ref "JP1") (pin "32") (pinfunction "32_32") (pintype "passive"))
    )
    (net (code "116") (name "unconnected-(JP1-Pad33)") (class "Default")
      (node (ref "JP1") (pin "33") (pinfunction "33_33") (pintype "passive"))
    )
    (net (code "117") (name "unconnected-(JP1-Pad34)") (class "Default")
      (node (ref "JP1") (pin "34") (pinfunction "34_34") (pintype "passive"))
    )
    (net (code "118") (name "unconnected-(JP1-Pad35)") (class "Default")
      (node (ref "JP1") (pin "35") (pinfunction "35_35") (pintype "passive"))
    )
    (net (code "119") (name "unconnected-(JP1-Pad36)") (class "Default")
      (node (ref "JP1") (pin "36") (pinfunction "36_36") (pintype "passive"))
    )
    (net (code "120") (name "unconnected-(JP1-Pad37)") (class "Default")
      (node (ref "JP1") (pin "37") (pinfunction "37_37") (pintype "passive"))
    )
    (net (code "121") (name "unconnected-(JP1-Pad38)") (class "Default")
      (node (ref "JP1") (pin "38") (pinfunction "38_38") (pintype "passive"))
    )
    (net (code "122") (name "unconnected-(JP1-Pad39)") (class "Default")
      (node (ref "JP1") (pin "39") (pinfunction "39_39") (pintype "passive"))
    )
    (net (code "123") (name "unconnected-(JP1-Pad40)") (class "Default")
      (node (ref "JP1") (pin "40") (pinfunction "40_40") (pintype "passive"))
    )
    (net (code "124") (name "unconnected-(R1-Pad1)") (class "Default")
      (node (ref "R1") (pin "1") (pinfunction "1_1") (pintype "passive"))
    )
    (net (code "125") (name "unconnected-(R1-Pad2)") (class "Default")
      (node (ref "R1") (pin "2") (pinfunction "2_2") (pintype "passive"))
    )
    (net (code "126") (name "unconnected-(X1-KEY-Pad4)") (class "Default")
      (node (ref "X1") (pin "4") (pinfunction "KEY_4") (pintype "bidirectional"))
    )
    (net (code "127") (name "unconnected-(X5-Pad1)") (class "Default")
      (node (ref "X5") (pin "1") (pinfunction "1_1") (pintype "passive"))
    )
    (net (code "128") (name "unconnected-(X5-Pad2)") (class "Default")
      (node (ref "X5") (pin "2") (pinfunction "2_2") (pintype "passive"))
    )
    (net (code "129") (name "unconnected-(X5-Pad3)") (class "Default")
      (node (ref "X5") (pin "3") (pinfunction "3_3") (pintype "passive"))
    )
    (net (code "130") (name "unconnected-(X5-Pad4)") (class "Default")
      (node (ref "X5") (pin "4") (pinfunction "4_4") (pintype "passive"))
    )
    (net (code "131") (name "unconnected-(X5-Pad5)") (class "Default")
      (node (ref "X5") (pin "5") (pinfunction "5_5") (pintype "passive"))
    )
    (net (code "132") (name "unconnected-(X5-Pad6)") (class "Default")
      (node (ref "X5") (pin "6") (pinfunction "6_6") (pintype "passive"))
    )
    (net (code "133") (name "unconnected-(X5-Pad7)") (class "Default")
      (node (ref "X5") (pin "7") (pinfunction "7_7") (pintype "passive"))
    )
    (net (code "134") (name "unconnected-(X5-Pad8)") (class "Default")
      (node (ref "X5") (pin "8") (pinfunction "8_8") (pintype "passive"))
    )
    (net (code "135") (name "unconnected-(X5-Pad9)") (class "Default")
      (node (ref "X5") (pin "9") (pinfunction "9_9") (pintype "passive"))
    )
    (net (code "136") (name "unconnected-(X5-Pad10)") (class "Default")
      (node (ref "X5") (pin "10") (pinfunction "10_10") (pintype "passive"))
    )
    (net (code "137") (name "unconnected-(X5-Pad11)") (class "Default")
      (node (ref "X5") (pin "11") (pinfunction "11_11") (pintype "passive"))
    )
    (net (code "138") (name "unconnected-(X5-Pad12)") (class "Default")
      (node (ref "X5") (pin "12") (pinfunction "12_12") (pintype "passive"))
    )
    (net (code "139") (name "unconnected-(X5-Pad13)") (class "Default")
      (node (ref "X5") (pin "13") (pinfunction "13_13") (pintype "passive"))
    )
    (net (code "140") (name "unconnected-(X5-Pad14)") (class "Default")
      (node (ref "X5") (pin "14") (pinfunction "14_14") (pintype "passive"))
    )
    (net (code "141") (name "unconnected-(X5-Pad15)") (class "Default")
      (node (ref "X5") (pin "15") (pinfunction "15_15") (pintype "passive"))
    )
    (net (code "142") (name "unconnected-(X5-Pad16)") (class "Default")
      (node (ref "X5") (pin "16") (pinfunction "16_16") (pintype "passive"))
    )
    (net (code "143") (name "unconnected-(X5-Pad17)") (class "Default")
      (node (ref "X5") (pin "17") (pinfunction "17_17") (pintype "passive"))
    )
    (net (code "144") (name "unconnected-(X5-Pad18)") (class "Default")
      (node (ref "X5") (pin "18") (pinfunction "18_18") (pintype "passive"))
    )
    (net (code "145") (name "unconnected-(X5-Pad19)") (class "Default")
      (node (ref "X5") (pin "19") (pinfunction "19_19") (pintype "passive"))
    )
    (net (code "146") (name "unconnected-(X5-Pad20)") (class "Default")
      (node (ref "X5") (pin "20") (pinfunction "20_20") (pintype "passive"))
    )
    (net (code "147") (name "unconnected-(X5-Pad21)") (class "Default")
      (node (ref "X5") (pin "21") (pinfunction "21_21") (pintype "passive"))
    )
    (net (code "148") (name "unconnected-(X5-Pad22)") (class "Default")
      (node (ref "X5") (pin "22") (pinfunction "22_22") (pintype "passive"))
    )
    (net (code "149") (name "unconnected-(X5-Pad23)") (class "Default")
      (node (ref "X5") (pin "23") (pinfunction "23_23") (pintype "passive"))
    )
    (net (code "150") (name "unconnected-(X5-Pad24)") (class "Default")
      (node (ref "X5") (pin "24") (pinfunction "24_24") (pintype "passive"))
    )
    (net (code "151") (name "unconnected-(X5-Pad25)") (class "Default")
      (node (ref "X5") (pin "25") (pinfunction "25_25") (pintype "passive"))
    )
  )
)
